# F2.net
KiCad netlist of a schematic drawn in EAGLE
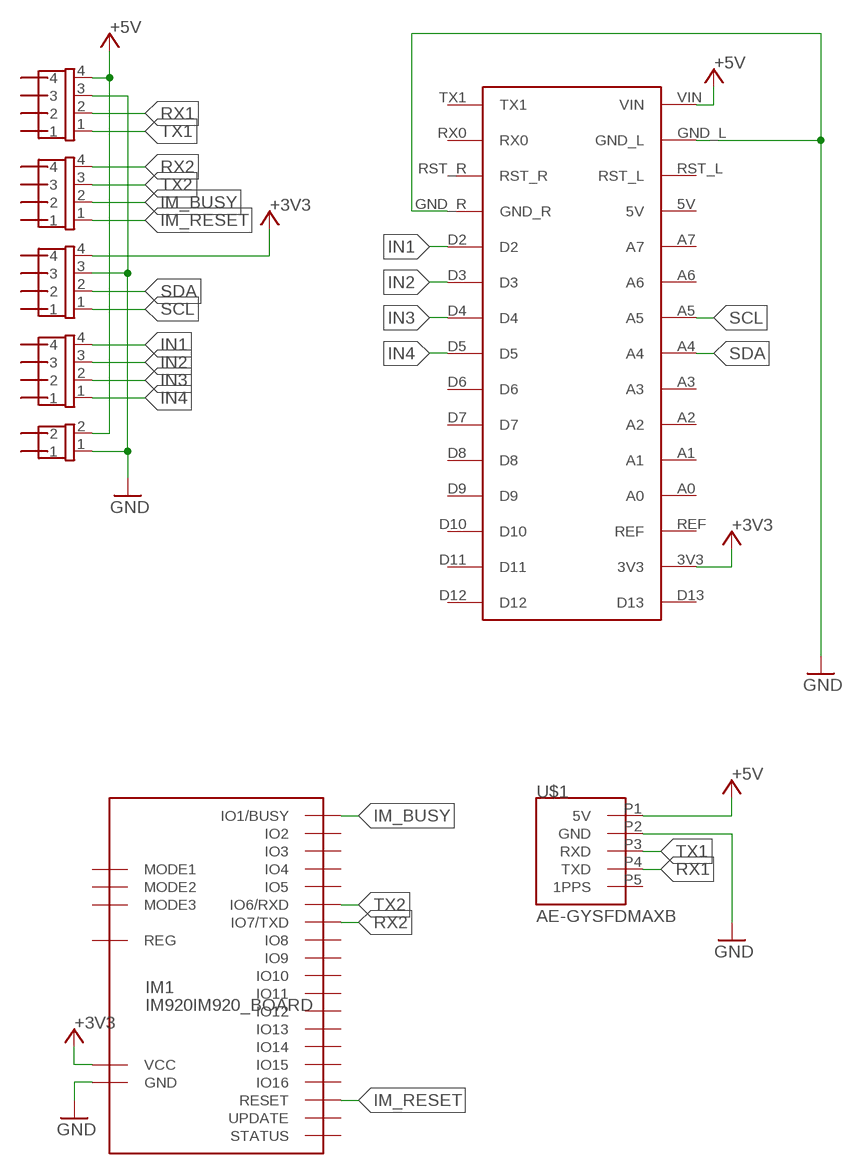
[diagram p0: schematic, sheet 1]

(export (version "E")
  (design (tool "Eeschema 10.0.6"))
  (components
    (comp (ref "ARDUINO_NANO2")
      (value "ARDUINO_NANO")
      (footprint "eagle-import:ARDUINO_NANO")
      (libsource (lib "eagle-import") (part "ARDUINO_NANO"))
    )
    (comp (ref "CONN1")
      (value "4PIN")
      (footprint "eagle-import:4PIN")
      (libsource (lib "eagle-import") (part "4PIN"))
    )
    (comp (ref "CONN2")
      (value "4PIN")
      (footprint "eagle-import:4PIN")
      (libsource (lib "eagle-import") (part "4PIN"))
    )
    (comp (ref "CONN3")
      (value "4PIN")
      (footprint "eagle-import:4PIN")
      (libsource (lib "eagle-import") (part "4PIN"))
    )
    (comp (ref "CONN4")
      (value "4PIN")
      (footprint "eagle-import:4PIN")
      (libsource (lib "eagle-import") (part "4PIN"))
    )
    (comp (ref "CONN5")
      (value "2PIN")
      (footprint "eagle-import:2PIN")
      (libsource (lib "eagle-import") (part "2PIN"))
    )
    (comp (ref "IM1")
      (value "IM920IM920_BOARD")
      (footprint "eagle-import:IM920_BOARD")
      (libsource (lib "eagle-import") (part "IM920IM920_BOARD"))
    )
    (comp (ref "U$1")
      (value "AE-GYSFDMAXB")
      (footprint "eagle-import:AE-GYSFDMAXB")
      (libsource (lib "eagle-import") (part "AE-GYSFDMAXB"))
    )
  )
  (nets
    (net (code "1") (name "+3V3") (class "Default")
      (node (ref "ARDUINO_NANO2") (pin "3V3") (pinfunction "3V3_3V3") (pintype "bidirectional"))
      (node (ref "CONN3") (pin "4") (pinfunction "4_4") (pintype "bidirectional"))
      (node (ref "IM1") (pin "IO23") (pinfunction "VCC_IO23") (pintype "bidirectional"))
    )
    (net (code "2") (name "+5V") (class "Default")
      (node (ref "ARDUINO_NANO2") (pin "VIN") (pinfunction "VIN_VIN") (pintype "bidirectional"))
      (node (ref "CONN1") (pin "4") (pinfunction "4_4") (pintype "bidirectional"))
      (node (ref "CONN5") (pin "2") (pinfunction "2_2") (pintype "bidirectional"))
      (node (ref "U$1") (pin "P1") (pinfunction "5V_P1") (pintype "bidirectional"))
    )
    (net (code "3") (name "GND") (class "Default")
      (node (ref "ARDUINO_NANO2") (pin "GND_L") (pinfunction "GND_L_GND_L") (pintype "bidirectional"))
      (node (ref "ARDUINO_NANO2") (pin "GND_R") (pinfunction "GND_R_GND_R") (pintype "bidirectional"))
      (node (ref "CONN1") (pin "3") (pinfunction "3_3") (pintype "bidirectional"))
      (node (ref "CONN3") (pin "3") (pinfunction "3_3") (pintype "bidirectional"))
      (node (ref "CONN5") (pin "1") (pinfunction "1_1") (pintype "bidirectional"))
      (node (ref "IM1") (pin "IO24") (pinfunction "GND_IO24") (pintype "bidirectional"))
      (node (ref "U$1") (pin "P2") (pinfunction "GND_P2") (pintype "bidirectional"))
    )
    (net (code "4") (name "IM_BUSY") (class "Default")
      (node (ref "CONN2") (pin "2") (pinfunction "2_2") (pintype "bidirectional"))
      (node (ref "IM1") (pin "IO1") (pinfunction "IO1/BUSY_IO1") (pintype "bidirectional"))
    )
    (net (code "5") (name "IM_RESET") (class "Default")
      (node (ref "CONN2") (pin "1") (pinfunction "1_1") (pintype "bidirectional"))
      (node (ref "IM1") (pin "IO25") (pinfunction "RESET_IO25") (pintype "bidirectional"))
    )
    (net (code "6") (name "IN1") (class "Default")
      (node (ref "ARDUINO_NANO2") (pin "D2") (pinfunction "D2_D2") (pintype "bidirectional"))
      (node (ref "CONN4") (pin "4") (pinfunction "4_4") (pintype "bidirectional"))
    )
    (net (code "7") (name "IN2") (class "Default")
      (node (ref "ARDUINO_NANO2") (pin "D3") (pinfunction "D3_D3") (pintype "bidirectional"))
      (node (ref "CONN4") (pin "3") (pinfunction "3_3") (pintype "bidirectional"))
    )
    (net (code "8") (name "IN3") (class "Default")
      (node (ref "ARDUINO_NANO2") (pin "D4") (pinfunction "D4_D4") (pintype "bidirectional"))
      (node (ref "CONN4") (pin "2") (pinfunction "2_2") (pintype "bidirectional"))
    )
    (net (code "9") (name "IN4") (class "Default")
      (node (ref "ARDUINO_NANO2") (pin "D5") (pinfunction "D5_D5") (pintype "bidirectional"))
      (node (ref "CONN4") (pin "1") (pinfunction "1_1") (pintype "bidirectional"))
    )
    (net (code "10") (name "RX1") (class "Default")
      (node (ref "CONN1") (pin "2") (pinfunction "2_2") (pintype "bidirectional"))
      (node (ref "U$1") (pin "P4") (pinfunction "TXD_P4") (pintype "bidirectional"))
    )
    (net (code "11") (name "RX2") (class "Default")
      (node (ref "CONN2") (pin "4") (pinfunction "4_4") (pintype "bidirectional"))
      (node (ref "IM1") (pin "IO7") (pinfunction "IO7/TXD_IO7") (pintype "bidirectional"))
    )
    (net (code "12") (name "SCL") (class "Default")
      (node (ref "ARDUINO_NANO2") (pin "A5") (pinfunction "A5_A5") (pintype "bidirectional"))
      (node (ref "CONN3") (pin "1") (pinfunction "1_1") (pintype "bidirectional"))
    )
    (net (code "13") (name "SDA") (class "Default")
      (node (ref "ARDUINO_NANO2") (pin "A4") (pinfunction "A4_A4") (pintype "bidirectional"))
      (node (ref "CONN3") (pin "2") (pinfunction "2_2") (pintype "bidirectional"))
    )
    (net (code "14") (name "TX1") (class "Default")
      (node (ref "CONN1") (pin "1") (pinfunction "1_1") (pintype "bidirectional"))
      (node (ref "U$1") (pin "P3") (pinfunction "RXD_P3") (pintype "bidirectional"))
    )
    (net (code "15") (name "TX2") (class "Default")
      (node (ref "CONN2") (pin "3") (pinfunction "3_3") (pintype "bidirectional"))
      (node (ref "IM1") (pin "IO6") (pinfunction "IO6/RXD_IO6") (pintype "bidirectional"))
    )
    (net (code "16") (name "unconnected-(ARDUINO_NANO2-Pad5V)") (class "Default")
      (node (ref "ARDUINO_NANO2") (pin "5V") (pinfunction "5V_5V") (pintype "bidirectional"))
    )
    (net (code "17") (name "unconnected-(ARDUINO_NANO2-PadA0)") (class "Default")
      (node (ref "ARDUINO_NANO2") (pin "A0") (pinfunction "A0_A0") (pintype "bidirectional"))
    )
    (net (code "18") (name "unconnected-(ARDUINO_NANO2-PadA1)") (class "Default")
      (node (ref "ARDUINO_NANO2") (pin "A1") (pinfunction "A1_A1") (pintype "bidirectional"))
    )
    (net (code "19") (name "unconnected-(ARDUINO_NANO2-PadA2)") (class "Default")
      (node (ref "ARDUINO_NANO2") (pin "A2") (pinfunction "A2_A2") (pintype "bidirectional"))
    )
    (net (code "20") (name "unconnected-(ARDUINO_NANO2-PadA3)") (class "Default")
      (node (ref "ARDUINO_NANO2") (pin "A3") (pinfunction "A3_A3") (pintype "bidirectional"))
    )
    (net (code "21") (name "unconnected-(ARDUINO_NANO2-PadA6)") (class "Default")
      (node (ref "ARDUINO_NANO2") (pin "A6") (pinfunction "A6_A6") (pintype "bidirectional"))
    )
    (net (code "22") (name "unconnected-(ARDUINO_NANO2-PadA7)") (class "Default")
      (node (ref "ARDUINO_NANO2") (pin "A7") (pinfunction "A7_A7") (pintype "bidirectional"))
    )
    (net (code "23") (name "unconnected-(ARDUINO_NANO2-PadD6)") (class "Default")
      (node (ref "ARDUINO_NANO2") (pin "D6") (pinfunction "D6_D6") (pintype "bidirectional"))
    )
    (net (code "24") (name "unconnected-(ARDUINO_NANO2-PadD7)") (class "Default")
      (node (ref "ARDUINO_NANO2") (pin "D7") (pinfunction "D7_D7") (pintype "bidirectional"))
    )
    (net (code "25") (name "unconnected-(ARDUINO_NANO2-PadD8)") (class "Default")
      (node (ref "ARDUINO_NANO2") (pin "D8") (pinfunction "D8_D8") (pintype "bidirectional"))
    )
    (net (code "26") (name "unconnected-(ARDUINO_NANO2-PadD9)") (class "Default")
      (node (ref "ARDUINO_NANO2") (pin "D9") (pinfunction "D9_D9") (pintype "bidirectional"))
    )
    (net (code "27") (name "unconnected-(ARDUINO_NANO2-PadD10)") (class "Default")
      (node (ref "ARDUINO_NANO2") (pin "D10") (pinfunction "D10_D10") (pintype "bidirectional"))
    )
    (net (code "28") (name "unconnected-(ARDUINO_NANO2-PadD11)") (class "Default")
      (node (ref "ARDUINO_NANO2") (pin "D11") (pinfunction "D11_D11") (pintype "bidirectional"))
    )
    (net (code "29") (name "unconnected-(ARDUINO_NANO2-PadD12)") (class "Default")
      (node (ref "ARDUINO_NANO2") (pin "D12") (pinfunction "D12_D12") (pintype "bidirectional"))
    )
    (net (code "30") (name "unconnected-(ARDUINO_NANO2-PadD13)") (class "Default")
      (node (ref "ARDUINO_NANO2") (pin "D13") (pinfunction "D13_D13") (pintype "bidirectional"))
    )
    (net (code "31") (name "unconnected-(ARDUINO_NANO2-PadREF)") (class "Default")
      (node (ref "ARDUINO_NANO2") (pin "REF") (pinfunction "REF_REF") (pintype "bidirectional"))
    )
    (net (code "32") (name "unconnected-(ARDUINO_NANO2-PadRST_L)") (class "Default")
      (node (ref "ARDUINO_NANO2") (pin "RST_L") (pinfunction "RST_L_RST_L") (pintype "bidirectional"))
    )
    (net (code "33") (name "unconnected-(ARDUINO_NANO2-PadRST_R)") (class "Default")
      (node (ref "ARDUINO_NANO2") (pin "RST_R") (pinfunction "RST_R_RST_R") (pintype "bidirectional"))
    )
    (net (code "34") (name "unconnected-(ARDUINO_NANO2-PadRX0)") (class "Default")
      (node (ref "ARDUINO_NANO2") (pin "RX0") (pinfunction "RX0_RX0") (pintype "bidirectional"))
    )
    (net (code "35") (name "unconnected-(ARDUINO_NANO2-PadTX1)") (class "Default")
      (node (ref "ARDUINO_NANO2") (pin "TX1") (pinfunction "TX1_TX1") (pintype "bidirectional"))
    )
    (net (code "36") (name "unconnected-(IM1-MODE1-PadIO17)") (class "Default")
      (node (ref "IM1") (pin "IO17") (pinfunction "MODE1_IO17") (pintype "bidirectional"))
    )
    (net (code "37") (name "unconnected-(IM1-MODE2-PadIO18)") (class "Default")
      (node (ref "IM1") (pin "IO18") (pinfunction "MODE2_IO18") (pintype "bidirectional"))
    )
    (net (code "38") (name "unconnected-(IM1-MODE3-PadIO19)") (class "Default")
      (node (ref "IM1") (pin "IO19") (pinfunction "MODE3_IO19") (pintype "bidirectional"))
    )
    (net (code "39") (name "unconnected-(IM1-PadIO2)") (class "Default")
      (node (ref "IM1") (pin "IO2") (pinfunction "IO2_IO2") (pintype "bidirectional"))
    )
    (net (code "40") (name "unconnected-(IM1-PadIO3)") (class "Default")
      (node (ref "IM1") (pin "IO3") (pinfunction "IO3_IO3") (pintype "bidirectional"))
    )
    (net (code "41") (name "unconnected-(IM1-PadIO4)") (class "Default")
      (node (ref "IM1") (pin "IO4") (pinfunction "IO4_IO4") (pintype "bidirectional"))
    )
    (net (code "42") (name "unconnected-(IM1-PadIO5)") (class "Default")
      (node (ref "IM1") (pin "IO5") (pinfunction "IO5_IO5") (pintype "bidirectional"))
    )
    (net (code "43") (name "unconnected-(IM1-PadIO8)") (class "Default")
      (node (ref "IM1") (pin "IO8") (pinfunction "IO8_IO8") (pintype "bidirectional"))
    )
    (net (code "44") (name "unconnected-(IM1-PadIO9)") (class "Default")
      (node (ref "IM1") (pin "IO9") (pinfunction "IO9_IO9") (pintype "bidirectional"))
    )
    (net (code "45") (name "unconnected-(IM1-PadIO10)") (class "Default")
      (node (ref "IM1") (pin "IO10") (pinfunction "IO10_IO10") (pintype "bidirectional"))
    )
    (net (code "46") (name "unconnected-(IM1-PadIO11)") (class "Default")
      (node (ref "IM1") (pin "IO11") (pinfunction "IO11_IO11") (pintype "bidirectional"))
    )
    (net (code "47") (name "unconnected-(IM1-PadIO12)") (class "Default")
      (node (ref "IM1") (pin "IO12") (pinfunction "IO12_IO12") (pintype "bidirectional"))
    )
    (net (code "48") (name "unconnected-(IM1-PadIO13)") (class "Default")
      (node (ref "IM1") (pin "IO13") (pinfunction "IO13_IO13") (pintype "bidirectional"))
    )
    (net (code "49") (name "unconnected-(IM1-PadIO14)") (class "Default")
      (node (ref "IM1") (pin "IO14") (pinfunction "IO14_IO14") (pintype "bidirectional"))
    )
    (net (code "50") (name "unconnected-(IM1-PadIO15)") (class "Default")
      (node (ref "IM1") (pin "IO15") (pinfunction "IO15_IO15") (pintype "bidirectional"))
    )
    (net (code "51") (name "unconnected-(IM1-PadIO16)") (class "Default")
      (node (ref "IM1") (pin "IO16") (pinfunction "IO16_IO16") (pintype "bidirectional"))
    )
    (net (code "52") (name "unconnected-(IM1-REG-PadIO22)") (class "Default")
      (node (ref "IM1") (pin "IO22") (pinfunction "REG_IO22") (pintype "bidirectional"))
    )
    (net (code "53") (name "unconnected-(IM1-STATUS-PadIO21)") (class "Default")
      (node (ref "IM1") (pin "IO21") (pinfunction "STATUS_IO21") (pintype "bidirectional"))
    )
    (net (code "54") (name "unconnected-(IM1-UPDATE-PadIO20)") (class "Default")
      (node (ref "IM1") (pin "IO20") (pinfunction "UPDATE_IO20") (pintype "bidirectional"))
    )
    (net (code "55") (name "unconnected-(U$1-1PPS-PadP5)") (class "Default")
      (node (ref "U$1") (pin "P5") (pinfunction "1PPS_P5") (pintype "bidirectional"))
    )
  )
)
